# MainPCB.net
KiCad netlist of a schematic drawn in Altium Designer
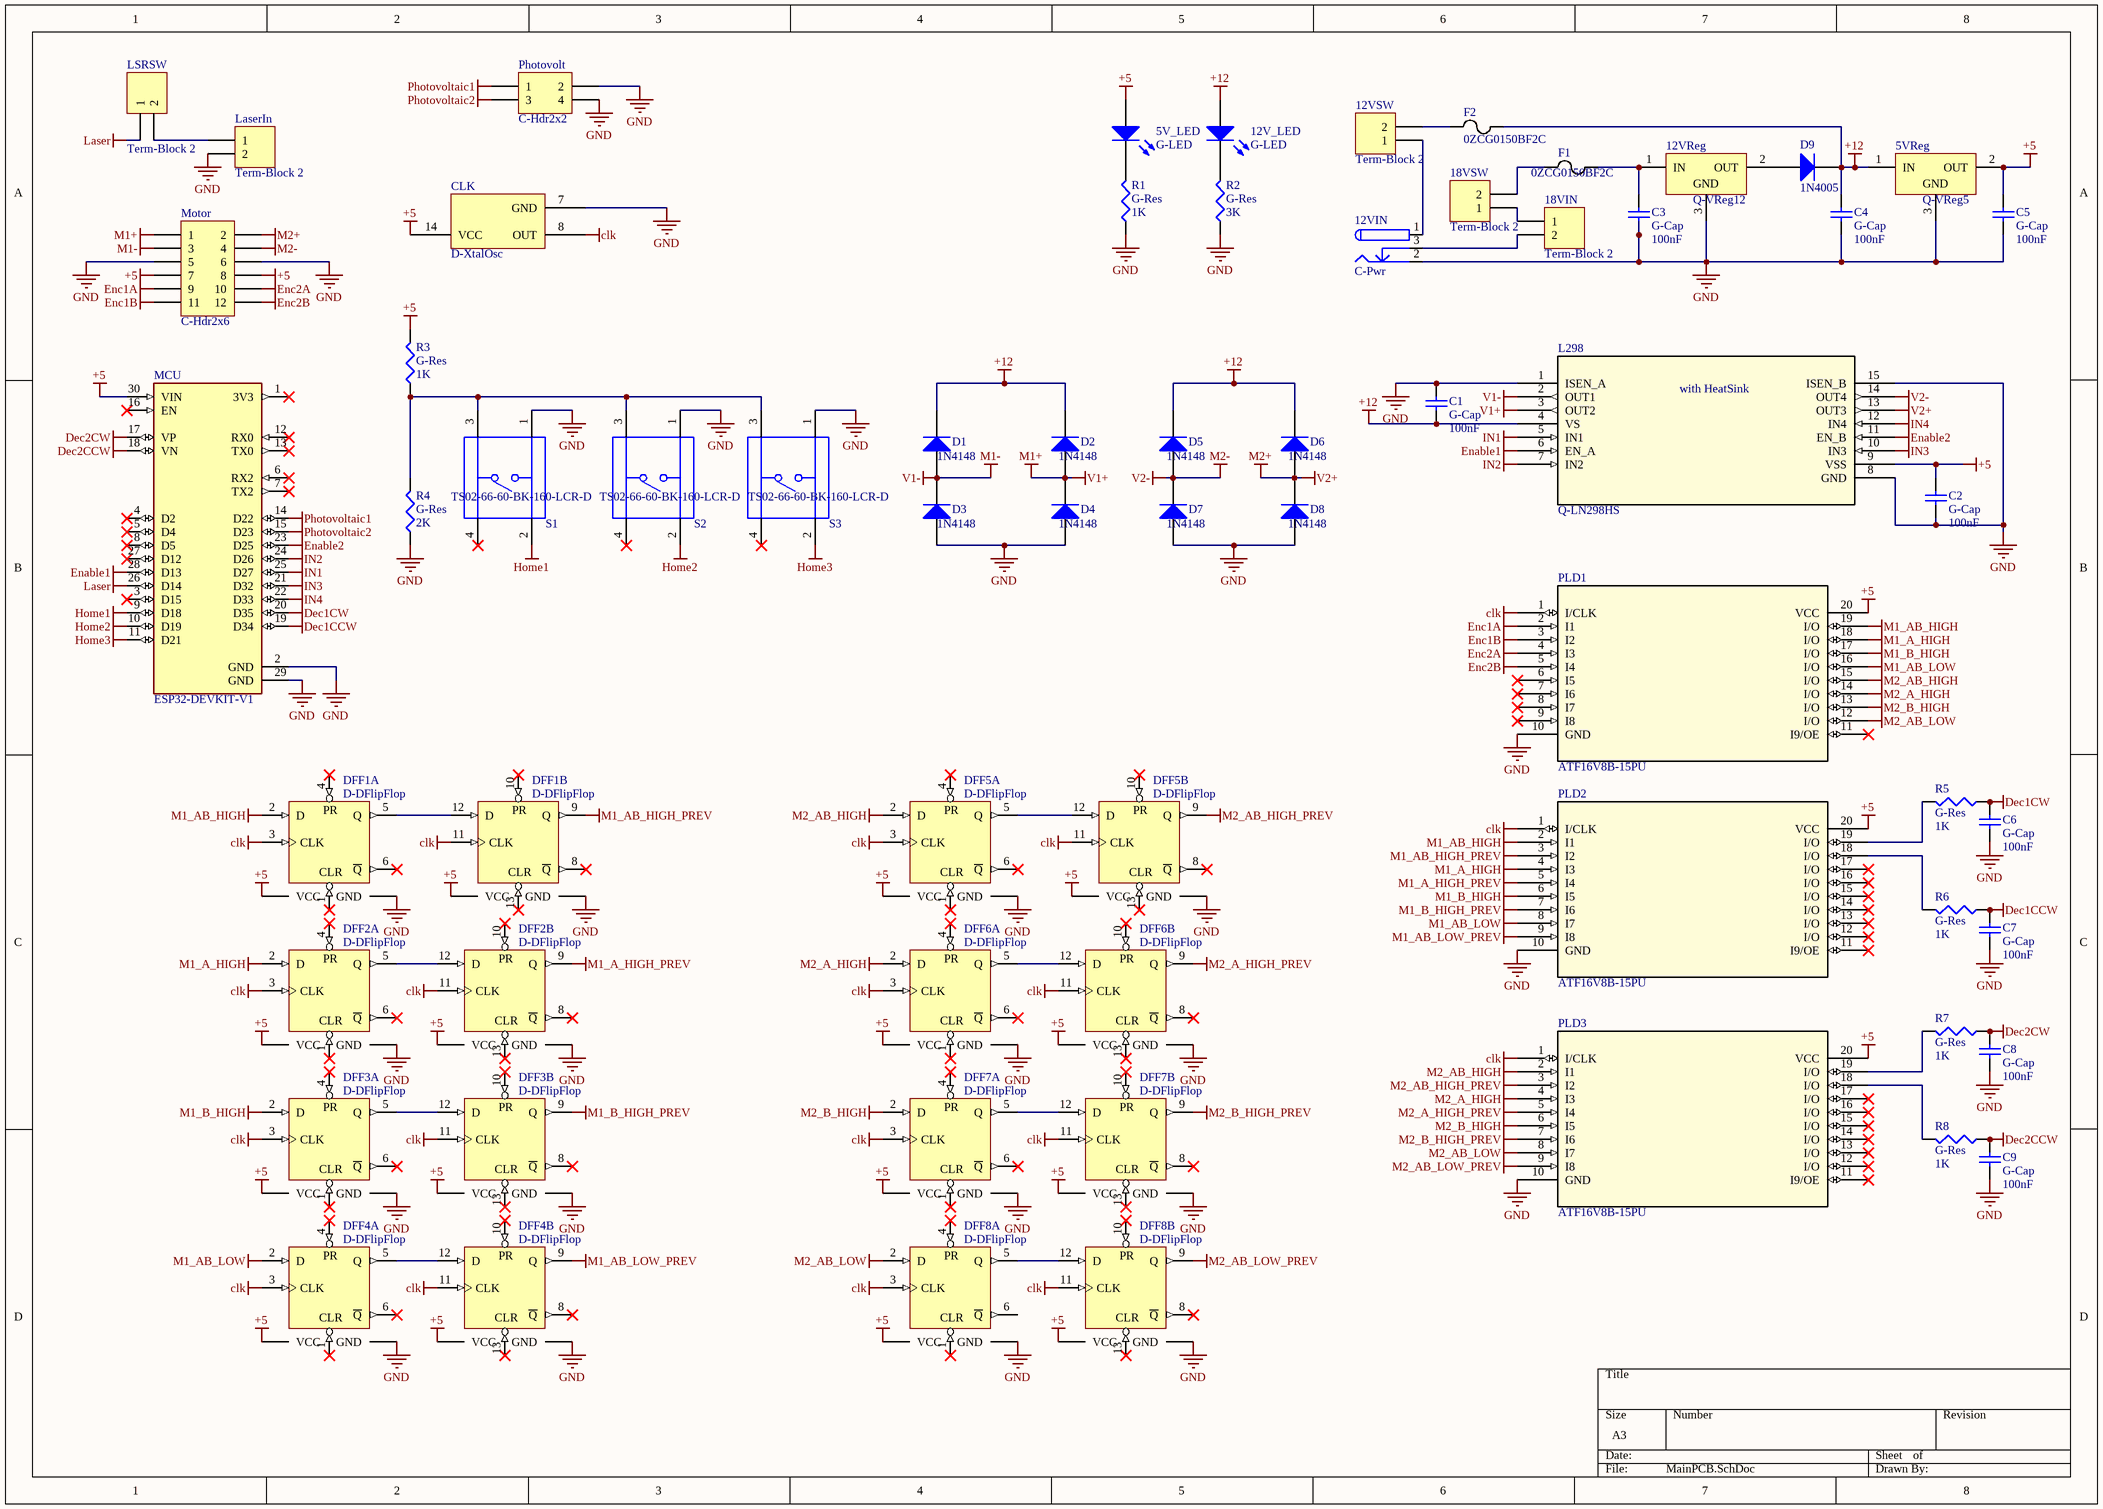
[diagram p0: MainPCB.SchDoc]

(export (version "E")
  (design (tool "Eeschema 10.0.6"))
  (components
    (comp (ref "5VReg")
      (value "Q-VReg5")
      (footprint "TO220_XLGE1.2")
      (description "voltage reg (5V)")
      (fields (field (name "PUBLISHER") "Altium Limited"))
      (libsource (lib "PartsDatabaseV16.1") (part "Q-VReg5"))
    )
    (comp (ref "5V_LED")
      (value "G-LED")
      (footprint "LED_LGE1.0")
      (description "Typical RED, GREEN, YELLOW, AMBER GaAs LED")
      (fields (field (name "PUBLISHER") "Altium Limited"))
      (libsource (lib "PartsDatabaseV16.1") (part "G-LED"))
    )
    (comp (ref "12VIN")
      (value "C-Pwr")
      (footprint "KLD_XLGE1.2")
      (description "Low Voltage Power Supply Connector")
      (fields (field (name "PUBLISHER") "Altium Limited"))
      (libsource (lib "PartsDatabaseV16.1") (part "C-Pwr"))
    )
    (comp (ref "12VReg")
      (value "Q-VReg12")
      (footprint "TO220_XLGE1.2")
      (description "voltage reg (12V)")
      (libsource (lib "PartsDatabaseV16.1") (part "Q-VReg12"))
    )
    (comp (ref "12VSW")
      (value "Term-Block 2")
      (footprint "TERM-BLOCK-5.08MM-2POS")
      (description "Terminal-Block 1x2")
      (fields (field (name "PUBLISHER") "Altium Limited"))
      (libsource (lib "") (part "C-Block2_1"))
    )
    (comp (ref "12V_LED")
      (value "G-LED")
      (footprint "LED_LGE1.0")
      (description "Typical RED, GREEN, YELLOW, AMBER GaAs LED")
      (fields (field (name "PUBLISHER") "Altium Limited"))
      (libsource (lib "PartsDatabaseV16.1") (part "G-LED"))
    )
    (comp (ref "18VIN")
      (value "Term-Block 2")
      (footprint "TERM-BLOCK-5.08MM-2POS")
      (description "Terminal-Block 1x2")
      (fields (field (name "PUBLISHER") "Altium Limited"))
      (libsource (lib "PartsDatabaseV16.1") (part "C-Block2"))
    )
    (comp (ref "18VSW")
      (value "Term-Block 2")
      (footprint "TERM-BLOCK-5.08MM-2POS")
      (description "Terminal-Block 1x2")
      (fields (field (name "PUBLISHER") "Altium Limited"))
      (libsource (lib "") (part "C-Block2_1"))
    )
    (comp (ref "C1")
      (value "G-Cap")
      (footprint "Cap2.54mm_LGE1.0")
      (description "Capacitor (specify value)")
      (fields (field (name "ALTIUM_VALUE") "100nF") (field (name "PUBLISHER") "Altium Limited"))
      (libsource (lib "PartsDatabaseV16.1") (part "G-Cap"))
    )
    (comp (ref "C2")
      (value "G-Cap")
      (footprint "Cap2.54mm_LGE1.0")
      (description "Capacitor (specify value)")
      (fields (field (name "ALTIUM_VALUE") "100nF") (field (name "PUBLISHER") "Altium Limited"))
      (libsource (lib "PartsDatabaseV16.1") (part "G-Cap"))
    )
    (comp (ref "C3")
      (value "G-Cap")
      (footprint "Cap2.54mm_LGE1.0")
      (description "Capacitor (specify value)")
      (fields (field (name "ALTIUM_VALUE") "100nF") (field (name "PUBLISHER") "Altium Limited"))
      (libsource (lib "PartsDatabaseV16.1") (part "G-Cap"))
    )
    (comp (ref "C4")
      (value "G-Cap")
      (footprint "Cap2.54mm_LGE1.0")
      (description "Capacitor (specify value)")
      (fields (field (name "ALTIUM_VALUE") "100nF") (field (name "PUBLISHER") "Altium Limited"))
      (libsource (lib "PartsDatabaseV16.1") (part "G-Cap"))
    )
    (comp (ref "C5")
      (value "G-Cap")
      (footprint "Cap2.54mm_LGE1.0")
      (description "Capacitor (specify value)")
      (fields (field (name "ALTIUM_VALUE") "100nF") (field (name "PUBLISHER") "Altium Limited"))
      (libsource (lib "PartsDatabaseV16.1") (part "G-Cap"))
    )
    (comp (ref "C6")
      (value "G-Cap")
      (footprint "Cap2.54mm_LGE1.0")
      (description "Capacitor (specify value)")
      (fields (field (name "ALTIUM_VALUE") "100nF") (field (name "PUBLISHER") "Altium Limited"))
      (libsource (lib "PartsDatabaseV16.1") (part "G-Cap"))
    )
    (comp (ref "C7")
      (value "G-Cap")
      (footprint "Cap2.54mm_LGE1.0")
      (description "Capacitor (specify value)")
      (fields (field (name "ALTIUM_VALUE") "100nF") (field (name "PUBLISHER") "Altium Limited"))
      (libsource (lib "PartsDatabaseV16.1") (part "G-Cap"))
    )
    (comp (ref "C8")
      (value "G-Cap")
      (footprint "Cap2.54mm_LGE1.0")
      (description "Capacitor (specify value)")
      (fields (field (name "ALTIUM_VALUE") "100nF") (field (name "PUBLISHER") "Altium Limited"))
      (libsource (lib "PartsDatabaseV16.1") (part "G-Cap"))
    )
    (comp (ref "C9")
      (value "G-Cap")
      (footprint "Cap2.54mm_LGE1.0")
      (description "Capacitor (specify value)")
      (fields (field (name "ALTIUM_VALUE") "100nF") (field (name "PUBLISHER") "Altium Limited"))
      (libsource (lib "PartsDatabaseV16.1") (part "G-Cap"))
    )
    (comp (ref "CLK")
      (value "D-XtalOsc")
      (footprint "4Lead Osc_LGE1.0")
      (description "Crystal Oscillator")
      (fields (field (name "PUBLISHER") "Altium Limited"))
      (libsource (lib "PartsDatabaseV16.1") (part "D-XtalOsc"))
    )
    (comp (ref "D1")
      (value "1N4148")
      (footprint "DO-41_XLGE1.2")
      (description "High-speed Diode")
      (libsource (lib "PartsDatabaseV16.1") (part "T-DiodeRect"))
    )
    (comp (ref "D2")
      (value "1N4148")
      (footprint "DO-41_XLGE1.2")
      (description "High-speed Diode")
      (libsource (lib "PartsDatabaseV16.1") (part "T-DiodeRect"))
    )
    (comp (ref "D3")
      (value "1N4148")
      (footprint "DO-41_XLGE1.2")
      (description "High-speed Diode")
      (libsource (lib "PartsDatabaseV16.1") (part "T-DiodeRect"))
    )
    (comp (ref "D4")
      (value "1N4148")
      (footprint "DO-41_XLGE1.2")
      (description "High-speed Diode")
      (libsource (lib "PartsDatabaseV16.1") (part "T-DiodeRect"))
    )
    (comp (ref "D5")
      (value "1N4148")
      (footprint "DO-41_XLGE1.2")
      (description "High-speed Diode")
      (libsource (lib "PartsDatabaseV16.1") (part "T-DiodeRect"))
    )
    (comp (ref "D6")
      (value "1N4148")
      (footprint "DO-41_XLGE1.2")
      (description "High-speed Diode")
      (libsource (lib "PartsDatabaseV16.1") (part "T-DiodeRect"))
    )
    (comp (ref "D7")
      (value "1N4148")
      (footprint "DO-41_XLGE1.2")
      (description "High-speed Diode")
      (libsource (lib "PartsDatabaseV16.1") (part "T-DiodeRect"))
    )
    (comp (ref "D8")
      (value "1N4148")
      (footprint "DO-41_XLGE1.2")
      (description "High-speed Diode")
      (libsource (lib "PartsDatabaseV16.1") (part "T-DiodeRect"))
    )
    (comp (ref "D9")
      (value "1N4005")
      (footprint "DO-41_XLGE1.2")
      (description "Diode")
      (fields (field (name "PUBLISHER") "Altium Limited"))
      (libsource (lib "PartsDatabaseV16.1") (part "T-Diode1N4005"))
    )
    (comp (ref "DFF1")
      (value "D-DFlipFlop")
      (footprint "DIP14_LGE1.0")
      (description "Dual D flip-flop")
      (fields (field (name "PUBLISHER") "Altium Limited"))
      (libsource (lib "PartsDatabaseV16.1") (part "D-DFlipFlop"))
    )
    (comp (ref "DFF2")
      (value "D-DFlipFlop")
      (footprint "DIP14_LGE1.0")
      (description "Dual D flip-flop")
      (fields (field (name "PUBLISHER") "Altium Limited"))
      (libsource (lib "PartsDatabaseV16.1") (part "D-DFlipFlop"))
    )
    (comp (ref "DFF3")
      (value "D-DFlipFlop")
      (footprint "DIP14_LGE1.0")
      (description "Dual D flip-flop")
      (fields (field (name "PUBLISHER") "Altium Limited"))
      (libsource (lib "PartsDatabaseV16.1") (part "D-DFlipFlop"))
    )
    (comp (ref "DFF4")
      (value "D-DFlipFlop")
      (footprint "DIP14_LGE1.0")
      (description "Dual D flip-flop")
      (fields (field (name "PUBLISHER") "Altium Limited"))
      (libsource (lib "PartsDatabaseV16.1") (part "D-DFlipFlop"))
    )
    (comp (ref "DFF5")
      (value "D-DFlipFlop")
      (footprint "DIP14_LGE1.0")
      (description "Dual D flip-flop")
      (fields (field (name "PUBLISHER") "Altium Limited"))
      (libsource (lib "PartsDatabaseV16.1") (part "D-DFlipFlop"))
    )
    (comp (ref "DFF6")
      (value "D-DFlipFlop")
      (footprint "DIP14_LGE1.0")
      (description "Dual D flip-flop")
      (fields (field (name "PUBLISHER") "Altium Limited"))
      (libsource (lib "PartsDatabaseV16.1") (part "D-DFlipFlop"))
    )
    (comp (ref "DFF7")
      (value "D-DFlipFlop")
      (footprint "DIP14_LGE1.0")
      (description "Dual D flip-flop")
      (fields (field (name "PUBLISHER") "Altium Limited"))
      (libsource (lib "PartsDatabaseV16.1") (part "D-DFlipFlop"))
    )
    (comp (ref "DFF8")
      (value "D-DFlipFlop")
      (footprint "DIP14_LGE1.0")
      (description "Dual D flip-flop")
      (fields (field (name "PUBLISHER") "Altium Limited"))
      (libsource (lib "PartsDatabaseV16.1") (part "D-DFlipFlop"))
    )
    (comp (ref "F1")
      (value "0ZCG0150BF2C")
      (footprint "0ZCG_BEL")
      (description "PTC RESET FUSE 24V 1.5A 1812")
      (libsource (lib "0ZCG0150BF2C") (part "0ZCG0150BF2C"))
    )
    (comp (ref "F2")
      (value "0ZCG0150BF2C")
      (footprint "0ZCG_BEL")
      (description "PTC RESET FUSE 24V 1.5A 1812")
      (libsource (lib "0ZCG0150BF2C") (part "0ZCG0150BF2C"))
    )
    (comp (ref "L298")
      (value "Q-LN298HS")
      (footprint "Multiwatt15_V_ELEC391HS")
      (description "LN298 - IC Bridge Driver Par 15Multiwatt")
      (fields
        (field (name "MANUFACTURER_PART_NUMBER") "L298N")
        (field (name "COPYRIGHT") "Copyright (C) 2015 Accelerated Designs. All rights reserved")
      )
      (libsource (lib "AdditionalParts391") (part "Q-LN298HS"))
    )
    (comp (ref "LaserIn")
      (value "Term-Block 2")
      (footprint "TERM-BLOCK-5.08MM-2POS")
      (description "Terminal-Block 1x2")
      (fields (field (name "PUBLISHER") "Altium Limited"))
      (libsource (lib "PartsDatabaseV16.1") (part "C-Block2"))
    )
    (comp (ref "LSRSW")
      (value "Term-Block 2")
      (footprint "TERM-BLOCK-5.08MM-2POS")
      (description "Terminal-Block 1x2")
      (fields (field (name "PUBLISHER") "Altium Limited"))
      (libsource (lib "") (part "C-Block2_2"))
    )
    (comp (ref "MCU")
      (value "ESP32-DEVKIT-V1")
      (footprint "MODULE_ESP32_DEVKIT_V1")
      (fields (field (name "MF") "Do it"))
      (libsource (lib "ESP32-DEVKIT-V1") (part "ESP32-DEVKIT-V1"))
    )
    (comp (ref "Motor")
      (value "C-Hdr2x6")
      (footprint "HDR2X6_LGE1.0")
      (description "Header, 6-Pin, Dual row")
      (fields (field (name "PUBLISHER") "Altium Limited"))
      (libsource (lib "PartsDatabaseV16.1") (part "C-Hdr2x6"))
    )
    (comp (ref "Photovolt")
      (value "C-Hdr2x2")
      (footprint "HDR2X2_LGE1.0")
      (description "Header, 2-Pin, Dual row")
      (fields (field (name "PUBLISHER") "Altium Limited"))
      (libsource (lib "PartsDatabaseV16.1") (part "C-Hdr2x2"))
    )
    (comp (ref "PLD1")
      (value "ATF16V8B-15PU")
      (footprint "20P3_ATM")
      (description "No Description Available")
      (libsource (lib "ATF16V8B-15PU") (part "ATF16V8B-15PU"))
    )
    (comp (ref "PLD2")
      (value "ATF16V8B-15PU")
      (footprint "20P3_ATM")
      (description "No Description Available")
      (libsource (lib "ATF16V8B-15PU") (part "ATF16V8B-15PU"))
    )
    (comp (ref "PLD3")
      (value "ATF16V8B-15PU")
      (footprint "20P3_ATM")
      (description "No Description Available")
      (libsource (lib "ATF16V8B-15PU") (part "ATF16V8B-15PU"))
    )
    (comp (ref "R1")
      (value "G-Res")
      (footprint "Res10mm_LGE1.0")
      (description "Resistor (specify value)")
      (fields (field (name "ALTIUM_VALUE") "1K") (field (name "PUBLISHER") "Altium Limited"))
      (libsource (lib "PartsDatabaseV16.1") (part "G-Res"))
    )
    (comp (ref "R2")
      (value "G-Res")
      (footprint "Res10mm_LGE1.0")
      (description "Resistor (specify value)")
      (fields (field (name "ALTIUM_VALUE") "3K") (field (name "PUBLISHER") "Altium Limited"))
      (libsource (lib "PartsDatabaseV16.1") (part "G-Res"))
    )
    (comp (ref "R3")
      (value "G-Res")
      (footprint "Res10mm_LGE1.0")
      (description "Resistor (specify value)")
      (fields (field (name "ALTIUM_VALUE") "1K") (field (name "PUBLISHER") "Altium Limited"))
      (libsource (lib "PartsDatabaseV16.1") (part "G-Res"))
    )
    (comp (ref "R4")
      (value "G-Res")
      (footprint "Res10mm_LGE1.0")
      (description "Resistor (specify value)")
      (fields (field (name "ALTIUM_VALUE") "2K") (field (name "PUBLISHER") "Altium Limited"))
      (libsource (lib "PartsDatabaseV16.1") (part "G-Res"))
    )
    (comp (ref "R5")
      (value "G-Res")
      (footprint "Res10mm_LGE1.0")
      (description "Resistor (specify value)")
      (fields (field (name "ALTIUM_VALUE") "1K") (field (name "PUBLISHER") "Altium Limited"))
      (libsource (lib "PartsDatabaseV16.1") (part "G-Res"))
    )
    (comp (ref "R6")
      (value "G-Res")
      (footprint "Res10mm_LGE1.0")
      (description "Resistor (specify value)")
      (fields (field (name "ALTIUM_VALUE") "1K") (field (name "PUBLISHER") "Altium Limited"))
      (libsource (lib "PartsDatabaseV16.1") (part "G-Res"))
    )
    (comp (ref "R7")
      (value "G-Res")
      (footprint "Res10mm_LGE1.0")
      (description "Resistor (specify value)")
      (fields (field (name "ALTIUM_VALUE") "1K") (field (name "PUBLISHER") "Altium Limited"))
      (libsource (lib "PartsDatabaseV16.1") (part "G-Res"))
    )
    (comp (ref "R8")
      (value "G-Res")
      (footprint "Res10mm_LGE1.0")
      (description "Resistor (specify value)")
      (fields (field (name "ALTIUM_VALUE") "1K") (field (name "PUBLISHER") "Altium Limited"))
      (libsource (lib "PartsDatabaseV16.1") (part "G-Res"))
    )
    (comp (ref "S1")
      (value "TS02-66-60-BK-160-LCR-D")
      (footprint "SW_TS02-66-60-BK-160-LCR-D")
      (description "6 x 6 mm, 6 mm Actuator Height, 160 gf, Black, Long Crimped, Through Hole, SPST, Tactile Switch")
      (fields (field (name "MF") "CUI Devices"))
      (libsource (lib "TS02-66-60-BK-160-LCR-D") (part "TS02-66-60-BK-160-LCR-D"))
    )
    (comp (ref "S2")
      (value "TS02-66-60-BK-160-LCR-D")
      (footprint "SW_TS02-66-60-BK-160-LCR-D")
      (description "6 x 6 mm, 6 mm Actuator Height, 160 gf, Black, Long Crimped, Through Hole, SPST, Tactile Switch")
      (fields (field (name "MF") "CUI Devices"))
      (libsource (lib "TS02-66-60-BK-160-LCR-D") (part "TS02-66-60-BK-160-LCR-D"))
    )
    (comp (ref "S3")
      (value "TS02-66-60-BK-160-LCR-D")
      (footprint "SW_TS02-66-60-BK-160-LCR-D")
      (description "6 x 6 mm, 6 mm Actuator Height, 160 gf, Black, Long Crimped, Through Hole, SPST, Tactile Switch")
      (fields (field (name "MF") "CUI Devices"))
      (libsource (lib "TS02-66-60-BK-160-LCR-D") (part "TS02-66-60-BK-160-LCR-D"))
    )
  )
  (nets
    (net (code "1") (name "+5") (class "Default")
      (node (ref "5VReg") (pin "2") (pinfunction "OUT_2") (pintype "power_in"))
      (node (ref "5V_LED") (pin "1") (pinfunction "A_1") (pintype "passive"))
      (node (ref "C2") (pin "1") (pinfunction "1_1") (pintype "passive"))
      (node (ref "C5") (pin "1") (pinfunction "1_1") (pintype "passive"))
      (node (ref "CLK") (pin "14") (pinfunction "VCC_14") (pintype "passive"))
      (node (ref "DFF1") (pin "14") (pinfunction "VCC_14") (pintype "power_in"))
      (node (ref "DFF2") (pin "14") (pinfunction "VCC_14") (pintype "power_in"))
      (node (ref "DFF3") (pin "14") (pinfunction "VCC_14") (pintype "power_in"))
      (node (ref "DFF4") (pin "14") (pinfunction "VCC_14") (pintype "power_in"))
      (node (ref "DFF5") (pin "14") (pinfunction "VCC_14") (pintype "power_in"))
      (node (ref "DFF6") (pin "14") (pinfunction "VCC_14") (pintype "power_in"))
      (node (ref "DFF7") (pin "14") (pinfunction "VCC_14") (pintype "power_in"))
      (node (ref "DFF8") (pin "14") (pinfunction "VCC_14") (pintype "power_in"))
      (node (ref "L298") (pin "9") (pinfunction "VSS_9") (pintype "power_in"))
      (node (ref "MCU") (pin "30") (pinfunction "VIN_30") (pintype "input"))
      (node (ref "Motor") (pin "7") (pinfunction "7_7") (pintype "passive"))
      (node (ref "Motor") (pin "8") (pinfunction "8_8") (pintype "passive"))
      (node (ref "PLD1") (pin "20") (pinfunction "VCC_20") (pintype "power_in"))
      (node (ref "PLD2") (pin "20") (pinfunction "VCC_20") (pintype "power_in"))
      (node (ref "PLD3") (pin "20") (pinfunction "VCC_20") (pintype "power_in"))
      (node (ref "R3") (pin "2") (pinfunction "2_2") (pintype "passive"))
    )
    (net (code "2") (name "+12") (class "Default")
      (node (ref "12V_LED") (pin "1") (pinfunction "A_1") (pintype "passive"))
      (node (ref "5VReg") (pin "1") (pinfunction "IN_1") (pintype "power_in"))
      (node (ref "C1") (pin "2") (pinfunction "2_2") (pintype "passive"))
      (node (ref "C4") (pin "1") (pinfunction "1_1") (pintype "passive"))
      (node (ref "D1") (pin "2") (pinfunction "K_2") (pintype "passive"))
      (node (ref "D2") (pin "2") (pinfunction "K_2") (pintype "passive"))
      (node (ref "D5") (pin "2") (pinfunction "K_2") (pintype "passive"))
      (node (ref "D6") (pin "2") (pinfunction "K_2") (pintype "passive"))
      (node (ref "D9") (pin "2") (pinfunction "K_2") (pintype "passive"))
      (node (ref "F2") (pin "2") (pinfunction "2_2") (pintype "passive"))
      (node (ref "L298") (pin "4") (pinfunction "VS_4") (pintype "power_in"))
    )
    (net (code "3") (name "Dec1CCW") (class "Default")
      (node (ref "C7") (pin "1") (pinfunction "1_1") (pintype "passive"))
      (node (ref "MCU") (pin "19") (pinfunction "D34_19") (pintype "bidirectional"))
      (node (ref "R6") (pin "1") (pinfunction "1_1") (pintype "passive"))
    )
    (net (code "4") (name "Dec1CW") (class "Default")
      (node (ref "C6") (pin "1") (pinfunction "1_1") (pintype "passive"))
      (node (ref "MCU") (pin "20") (pinfunction "D35_20") (pintype "bidirectional"))
      (node (ref "R5") (pin "1") (pinfunction "1_1") (pintype "passive"))
    )
    (net (code "5") (name "Dec2CCW") (class "Default")
      (node (ref "C9") (pin "1") (pinfunction "1_1") (pintype "passive"))
      (node (ref "MCU") (pin "18") (pinfunction "VN_18") (pintype "bidirectional"))
      (node (ref "R8") (pin "1") (pinfunction "1_1") (pintype "passive"))
    )
    (net (code "6") (name "Dec2CW") (class "Default")
      (node (ref "C8") (pin "1") (pinfunction "1_1") (pintype "passive"))
      (node (ref "MCU") (pin "17") (pinfunction "VP_17") (pintype "bidirectional"))
      (node (ref "R7") (pin "1") (pinfunction "1_1") (pintype "passive"))
    )
    (net (code "7") (name "Enable1") (class "Default")
      (node (ref "L298") (pin "6") (pinfunction "EN_A_6") (pintype "input"))
      (node (ref "MCU") (pin "28") (pinfunction "D13_28") (pintype "bidirectional"))
    )
    (net (code "8") (name "Enable2") (class "Default")
      (node (ref "L298") (pin "11") (pinfunction "EN_B_11") (pintype "input"))
      (node (ref "MCU") (pin "23") (pinfunction "D25_23") (pintype "bidirectional"))
    )
    (net (code "9") (name "Enc1A") (class "Default")
      (node (ref "Motor") (pin "9") (pinfunction "9_9") (pintype "passive"))
      (node (ref "PLD1") (pin "2") (pinfunction "I1_2") (pintype "input"))
    )
    (net (code "10") (name "Enc1B") (class "Default")
      (node (ref "Motor") (pin "11") (pinfunction "11_11") (pintype "passive"))
      (node (ref "PLD1") (pin "3") (pinfunction "I2_3") (pintype "input"))
    )
    (net (code "11") (name "Enc2A") (class "Default")
      (node (ref "Motor") (pin "10") (pinfunction "10_10") (pintype "passive"))
      (node (ref "PLD1") (pin "4") (pinfunction "I3_4") (pintype "input"))
    )
    (net (code "12") (name "Enc2B") (class "Default")
      (node (ref "Motor") (pin "12") (pinfunction "12_12") (pintype "passive"))
      (node (ref "PLD1") (pin "5") (pinfunction "I4_5") (pintype "input"))
    )
    (net (code "13") (name "GND") (class "Default")
      (node (ref "12VIN") (pin "2") (pinfunction "2_2") (pintype "power_in"))
      (node (ref "12VReg") (pin "3") (pinfunction "GND_3") (pintype "power_in"))
      (node (ref "5VReg") (pin "3") (pinfunction "GND_3") (pintype "power_in"))
      (node (ref "C1") (pin "1") (pinfunction "1_1") (pintype "passive"))
      (node (ref "C2") (pin "2") (pinfunction "2_2") (pintype "passive"))
      (node (ref "C3") (pin "2") (pinfunction "2_2") (pintype "passive"))
      (node (ref "C4") (pin "2") (pinfunction "2_2") (pintype "passive"))
      (node (ref "C5") (pin "2") (pinfunction "2_2") (pintype "passive"))
      (node (ref "C6") (pin "2") (pinfunction "2_2") (pintype "passive"))
      (node (ref "C7") (pin "2") (pinfunction "2_2") (pintype "passive"))
      (node (ref "C8") (pin "2") (pinfunction "2_2") (pintype "passive"))
      (node (ref "C9") (pin "2") (pinfunction "2_2") (pintype "passive"))
      (node (ref "CLK") (pin "7") (pinfunction "GND_7") (pintype "passive"))
      (node (ref "D3") (pin "1") (pinfunction "A_1") (pintype "passive"))
      (node (ref "D4") (pin "1") (pinfunction "A_1") (pintype "passive"))
      (node (ref "D7") (pin "1") (pinfunction "A_1") (pintype "passive"))
      (node (ref "D8") (pin "1") (pinfunction "A_1") (pintype "passive"))
      (node (ref "DFF1") (pin "7") (pinfunction "GND_7") (pintype "power_in"))
      (node (ref "DFF2") (pin "7") (pinfunction "GND_7") (pintype "power_in"))
      (node (ref "DFF3") (pin "7") (pinfunction "GND_7") (pintype "power_in"))
      (node (ref "DFF4") (pin "7") (pinfunction "GND_7") (pintype "power_in"))
      (node (ref "DFF5") (pin "7") (pinfunction "GND_7") (pintype "power_in"))
      (node (ref "DFF6") (pin "7") (pinfunction "GND_7") (pintype "power_in"))
      (node (ref "DFF7") (pin "7") (pinfunction "GND_7") (pintype "power_in"))
      (node (ref "DFF8") (pin "7") (pinfunction "GND_7") (pintype "power_in"))
      (node (ref "L298") (pin "1") (pinfunction "ISEN_A_1") (pintype "passive"))
      (node (ref "L298") (pin "15") (pinfunction "ISEN_B_15") (pintype "passive"))
      (node (ref "L298") (pin "8") (pinfunction "GND_8") (pintype "power_in"))
      (node (ref "LaserIn") (pin "2") (pinfunction "2_2") (pintype "passive"))
      (node (ref "MCU") (pin "2") (pinfunction "GND_2") (pintype "power_in"))
      (node (ref "MCU") (pin "29") (pinfunction "GND_29") (pintype "power_in"))
      (node (ref "Motor") (pin "5") (pinfunction "5_5") (pintype "passive"))
      (node (ref "Motor") (pin "6") (pinfunction "6_6") (pintype "passive"))
      (node (ref "PLD1") (pin "10") (pinfunction "GND_10") (pintype "power_in"))
      (node (ref "PLD2") (pin "10") (pinfunction "GND_10") (pintype "power_in"))
      (node (ref "PLD3") (pin "10") (pinfunction "GND_10") (pintype "power_in"))
      (node (ref "Photovolt") (pin "2") (pinfunction "2_2") (pintype "passive"))
      (node (ref "Photovolt") (pin "4") (pinfunction "4_4") (pintype "passive"))
      (node (ref "R1") (pin "1") (pinfunction "1_1") (pintype "passive"))
      (node (ref "R2") (pin "1") (pinfunction "1_1") (pintype "passive"))
      (node (ref "R4") (pin "1") (pinfunction "1_1") (pintype "passive"))
      (node (ref "S1") (pin "1") (pinfunction "1_1") (pintype "passive"))
      (node (ref "S2") (pin "1") (pinfunction "1_1") (pintype "passive"))
      (node (ref "S3") (pin "1") (pinfunction "1_1") (pintype "passive"))
    )
    (net (code "14") (name "Home1") (class "Default")
      (node (ref "MCU") (pin "9") (pinfunction "D18_9") (pintype "bidirectional"))
      (node (ref "S1") (pin "2") (pinfunction "2_2") (pintype "passive"))
    )
    (net (code "15") (name "Home2") (class "Default")
      (node (ref "MCU") (pin "10") (pinfunction "D19_10") (pintype "bidirectional"))
      (node (ref "S2") (pin "2") (pinfunction "2_2") (pintype "passive"))
    )
    (net (code "16") (name "Home3") (class "Default")
      (node (ref "MCU") (pin "11") (pinfunction "D21_11") (pintype "bidirectional"))
      (node (ref "S3") (pin "2") (pinfunction "2_2") (pintype "passive"))
    )
    (net (code "17") (name "IN1") (class "Default")
      (node (ref "L298") (pin "5") (pinfunction "IN1_5") (pintype "input"))
      (node (ref "MCU") (pin "25") (pinfunction "D27_25") (pintype "bidirectional"))
    )
    (net (code "18") (name "IN2") (class "Default")
      (node (ref "L298") (pin "7") (pinfunction "IN2_7") (pintype "input"))
      (node (ref "MCU") (pin "24") (pinfunction "D26_24") (pintype "bidirectional"))
    )
    (net (code "19") (name "IN3") (class "Default")
      (node (ref "L298") (pin "10") (pinfunction "IN3_10") (pintype "input"))
      (node (ref "MCU") (pin "21") (pinfunction "D32_21") (pintype "bidirectional"))
    )
    (net (code "20") (name "IN4") (class "Default")
      (node (ref "L298") (pin "12") (pinfunction "IN4_12") (pintype "input"))
      (node (ref "MCU") (pin "22") (pinfunction "D33_22") (pintype "bidirectional"))
    )
    (net (code "21") (name "Laser") (class "Default")
      (node (ref "LSRSW") (pin "1") (pinfunction "1_1") (pintype "passive"))
      (node (ref "MCU") (pin "26") (pinfunction "D14_26") (pintype "bidirectional"))
    )
    (net (code "22") (name "M1+") (class "Default")
      (node (ref "D2") (pin "1") (pinfunction "A_1") (pintype "passive"))
      (node (ref "D4") (pin "2") (pinfunction "K_2") (pintype "passive"))
      (node (ref "L298") (pin "3") (pinfunction "OUT2_3") (pintype "output"))
      (node (ref "Motor") (pin "1") (pinfunction "1_1") (pintype "passive"))
    )
    (net (code "23") (name "M1-") (class "Default")
      (node (ref "D1") (pin "1") (pinfunction "A_1") (pintype "passive"))
      (node (ref "D3") (pin "2") (pinfunction "K_2") (pintype "passive"))
      (node (ref "L298") (pin "2") (pinfunction "OUT1_2") (pintype "output"))
      (node (ref "Motor") (pin "3") (pinfunction "3_3") (pintype "passive"))
    )
    (net (code "24") (name "M1_AB_HIGH") (class "Default")
      (node (ref "DFF1") (pin "2") (pinfunction "D_2") (pintype "input"))
      (node (ref "PLD1") (pin "19") (pinfunction "I/O_19") (pintype "bidirectional"))
      (node (ref "PLD2") (pin "2") (pinfunction "I1_2") (pintype "input"))
    )
    (net (code "25") (name "M1_AB_HIGH_PREV") (class "Default")
      (node (ref "DFF1") (pin "9") (pinfunction "Q_9") (pintype "output"))
      (node (ref "PLD2") (pin "3") (pinfunction "I2_3") (pintype "input"))
    )
    (net (code "26") (name "M1_AB_LOW") (class "Default")
      (node (ref "DFF4") (pin "2") (pinfunction "D_2") (pintype "input"))
      (node (ref "PLD1") (pin "16") (pinfunction "I/O_16") (pintype "bidirectional"))
      (node (ref "PLD2") (pin "8") (pinfunction "I7_8") (pintype "input"))
    )
    (net (code "27") (name "M1_AB_LOW_PREV") (class "Default")
      (node (ref "DFF4") (pin "9") (pinfunction "Q_9") (pintype "output"))
      (node (ref "PLD2") (pin "9") (pinfunction "I8_9") (pintype "input"))
    )
    (net (code "28") (name "M1_A_HIGH") (class "Default")
      (node (ref "DFF2") (pin "2") (pinfunction "D_2") (pintype "input"))
      (node (ref "PLD1") (pin "18") (pinfunction "I/O_18") (pintype "bidirectional"))
      (node (ref "PLD2") (pin "4") (pinfunction "I3_4") (pintype "input"))
    )
    (net (code "29") (name "M1_A_HIGH_PREV") (class "Default")
      (node (ref "DFF2") (pin "9") (pinfunction "Q_9") (pintype "output"))
      (node (ref "PLD2") (pin "5") (pinfunction "I4_5") (pintype "input"))
    )
    (net (code "30") (name "M1_B_HIGH") (class "Default")
      (node (ref "DFF3") (pin "2") (pinfunction "D_2") (pintype "input"))
      (node (ref "PLD1") (pin "17") (pinfunction "I/O_17") (pintype "bidirectional"))
      (node (ref "PLD2") (pin "6") (pinfunction "I5_6") (pintype "input"))
    )
    (net (code "31") (name "M1_B_HIGH_PREV") (class "Default")
      (node (ref "DFF3") (pin "9") (pinfunction "Q_9") (pintype "output"))
      (node (ref "PLD2") (pin "7") (pinfunction "I6_7") (pintype "input"))
    )
    (net (code "32") (name "M2+") (class "Default")
      (node (ref "D6") (pin "1") (pinfunction "A_1") (pintype "passive"))
      (node (ref "D8") (pin "2") (pinfunction "K_2") (pintype "passive"))
      (node (ref "L298") (pin "13") (pinfunction "OUT3_13") (pintype "output"))
      (node (ref "Motor") (pin "2") (pinfunction "2_2") (pintype "passive"))
    )
    (net (code "33") (name "M2-") (class "Default")
      (node (ref "D5") (pin "1") (pinfunction "A_1") (pintype "passive"))
      (node (ref "D7") (pin "2") (pinfunction "K_2") (pintype "passive"))
      (node (ref "L298") (pin "14") (pinfunction "OUT4_14") (pintype "output"))
      (node (ref "Motor") (pin "4") (pinfunction "4_4") (pintype "passive"))
    )
    (net (code "34") (name "M2_AB_HIGH") (class "Default")
      (node (ref "DFF5") (pin "2") (pinfunction "D_2") (pintype "input"))
      (node (ref "PLD1") (pin "15") (pinfunction "I/O_15") (pintype "bidirectional"))
      (node (ref "PLD3") (pin "2") (pinfunction "I1_2") (pintype "input"))
    )
    (net (code "35") (name "M2_AB_HIGH_PREV") (class "Default")
      (node (ref "DFF5") (pin "9") (pinfunction "Q_9") (pintype "output"))
      (node (ref "PLD3") (pin "3") (pinfunction "I2_3") (pintype "input"))
    )
    (net (code "36") (name "M2_AB_LOW") (class "Default")
      (node (ref "DFF8") (pin "2") (pinfunction "D_2") (pintype "input"))
      (node (ref "PLD1") (pin "12") (pinfunction "I/O_12") (pintype "bidirectional"))
      (node (ref "PLD3") (pin "8") (pinfunction "I7_8") (pintype "input"))
    )
    (net (code "37") (name "M2_AB_LOW_PREV") (class "Default")
      (node (ref "DFF8") (pin "9") (pinfunction "Q_9") (pintype "output"))
      (node (ref "PLD3") (pin "9") (pinfunction "I8_9") (pintype "input"))
    )
    (net (code "38") (name "M2_A_HIGH") (class "Default")
      (node (ref "DFF6") (pin "2") (pinfunction "D_2") (pintype "input"))
      (node (ref "PLD1") (pin "14") (pinfunction "I/O_14") (pintype "bidirectional"))
      (node (ref "PLD3") (pin "4") (pinfunction "I3_4") (pintype "input"))
    )
    (net (code "39") (name "M2_A_HIGH_PREV") (class "Default")
      (node (ref "DFF6") (pin "9") (pinfunction "Q_9") (pintype "output"))
      (node (ref "PLD3") (pin "5") (pinfunction "I4_5") (pintype "input"))
    )
    (net (code "40") (name "M2_B_HIGH") (class "Default")
      (node (ref "DFF7") (pin "2") (pinfunction "D_2") (pintype "input"))
      (node (ref "PLD1") (pin "13") (pinfunction "I/O_13") (pintype "bidirectional"))
      (node (ref "PLD3") (pin "6") (pinfunction "I5_6") (pintype "input"))
    )
    (net (code "41") (name "M2_B_HIGH_PREV") (class "Default")
      (node (ref "DFF7") (pin "9") (pinfunction "Q_9") (pintype "output"))
      (node (ref "PLD3") (pin "7") (pinfunction "I6_7") (pintype "input"))
    )
    (net (code "42") (name "Net-(5V_LED-K)") (class "Default")
      (node (ref "5V_LED") (pin "2") (pinfunction "K_2") (pintype "passive"))
      (node (ref "R1") (pin "2") (pinfunction "2_2") (pintype "passive"))
    )
    (net (code "43") (name "Net-(12VIN-Pad1)") (class "Default")
      (node (ref "12VIN") (pin "1") (pinfunction "1_1") (pintype "power_in"))
      (node (ref "12VSW") (pin "1") (pinfunction "1_1") (pintype "passive"))
    )
    (net (code "44") (name "Net-(12VIN-Pad3)") (class "Default")
      (node (ref "12VIN") (pin "3") (pinfunction "3_3") (pintype "power_in"))
      (node (ref "18VIN") (pin "2") (pinfunction "2_2") (pintype "passive"))
    )
    (net (code "45") (name "Net-(12VReg-IN)") (class "Default")
      (node (ref "12VReg") (pin "1") (pinfunction "IN_1") (pintype "power_in"))
      (node (ref "C3") (pin "1") (pinfunction "1_1") (pintype "passive"))
      (node (ref "F1") (pin "2") (pinfunction "2_2") (pintype "passive"))
    )
    (net (code "46") (name "Net-(12VReg-OUT)") (class "Default")
      (node (ref "12VReg") (pin "2") (pinfunction "OUT_2") (pintype "power_in"))
      (node (ref "D9") (pin "1") (pinfunction "A_1") (pintype "passive"))
    )
    (net (code "47") (name "Net-(12VSW-Pad2)") (class "Default")
      (node (ref "12VSW") (pin "2") (pinfunction "2_2") (pintype "passive"))
      (node (ref "F2") (pin "1") (pinfunction "1_1") (pintype "passive"))
    )
    (net (code "48") (name "Net-(12V_LED-K)") (class "Default")
      (node (ref "12V_LED") (pin "2") (pinfunction "K_2") (pintype "passive"))
      (node (ref "R2") (pin "2") (pinfunction "2_2") (pintype "passive"))
    )
    (net (code "49") (name "Net-(18VIN-Pad1)") (class "Default")
      (node (ref "18VIN") (pin "1") (pinfunction "1_1") (pintype "passive"))
      (node (ref "18VSW") (pin "1") (pinfunction "1_1") (pintype "passive"))
    )
    (net (code "50") (name "Net-(18VSW-Pad2)") (class "Default")
      (node (ref "18VSW") (pin "2") (pinfunction "2_2") (pintype "passive"))
      (node (ref "F1") (pin "1") (pinfunction "1_1") (pintype "passive"))
    )
    (net (code "51") (name "Net-(DFF1A-Q)") (class "Default")
      (node (ref "DFF1") (pin "12") (pinfunction "D_12") (pintype "input"))
      (node (ref "DFF1") (pin "5") (pinfunction "Q_5") (pintype "output"))
    )
    (net (code "52") (name "Net-(DFF2A-Q)") (class "Default")
      (node (ref "DFF2") (pin "12") (pinfunction "D_12") (pintype "input"))
      (node (ref "DFF2") (pin "5") (pinfunction "Q_5") (pintype "output"))
    )
    (net (code "53") (name "Net-(DFF3A-Q)") (class "Default")
      (node (ref "DFF3") (pin "12") (pinfunction "D_12") (pintype "input"))
      (node (ref "DFF3") (pin "5") (pinfunction "Q_5") (pintype "output"))
    )
    (net (code "54") (name "Net-(DFF4A-Q)") (class "Default")
      (node (ref "DFF4") (pin "12") (pinfunction "D_12") (pintype "input"))
      (node (ref "DFF4") (pin "5") (pinfunction "Q_5") (pintype "output"))
    )
    (net (code "55") (name "Net-(DFF5A-Q)") (class "Default")
      (node (ref "DFF5") (pin "12") (pinfunction "D_12") (pintype "input"))
      (node (ref "DFF5") (pin "5") (pinfunction "Q_5") (pintype "output"))
    )
    (net (code "56") (name "Net-(DFF6A-Q)") (class "Default")
      (node (ref "DFF6") (pin "12") (pinfunction "D_12") (pintype "input"))
      (node (ref "DFF6") (pin "5") (pinfunction "Q_5") (pintype "output"))
    )
    (net (code "57") (name "Net-(DFF7A-Q)") (class "Default")
      (node (ref "DFF7") (pin "12") (pinfunction "D_12") (pintype "input"))
      (node (ref "DFF7") (pin "5") (pinfunction "Q_5") (pintype "output"))
    )
    (net (code "58") (name "Net-(DFF8A-Q)") (class "Default")
      (node (ref "DFF8") (pin "12") (pinfunction "D_12") (pintype "input"))
      (node (ref "DFF8") (pin "5") (pinfunction "Q_5") (pintype "output"))
    )
    (net (code "59") (name "Net-(LSRSW-Pad2)") (class "Default")
      (node (ref "LSRSW") (pin "2") (pinfunction "2_2") (pintype "passive"))
      (node (ref "LaserIn") (pin "1") (pinfunction "1_1") (pintype "passive"))
    )
    (net (code "60") (name "Net-(PLD2-I{slash}O-Pad18)") (class "Default")
      (node (ref "PLD2") (pin "18") (pinfunction "I/O_18") (pintype "bidirectional"))
      (node (ref "R6") (pin "2") (pinfunction "2_2") (pintype "passive"))
    )
    (net (code "61") (name "Net-(PLD2-I{slash}O-Pad19)") (class "Default")
      (node (ref "PLD2") (pin "19") (pinfunction "I/O_19") (pintype "bidirectional"))
      (node (ref "R5") (pin "2") (pinfunction "2_2") (pintype "passive"))
    )
    (net (code "62") (name "Net-(PLD3-I{slash}O-Pad18)") (class "Default")
      (node (ref "PLD3") (pin "18") (pinfunction "I/O_18") (pintype "bidirectional"))
      (node (ref "R8") (pin "2") (pinfunction "2_2") (pintype "passive"))
    )
    (net (code "63") (name "Net-(PLD3-I{slash}O-Pad19)") (class "Default")
      (node (ref "PLD3") (pin "19") (pinfunction "I/O_19") (pintype "bidirectional"))
      (node (ref "R7") (pin "2") (pinfunction "2_2") (pintype "passive"))
    )
    (net (code "64") (name "Net-(R3-Pad1)") (class "Default")
      (node (ref "R3") (pin "1") (pinfunction "1_1") (pintype "passive"))
      (node (ref "R4") (pin "2") (pinfunction "2_2") (pintype "passive"))
      (node (ref "S1") (pin "3") (pinfunction "3_3") (pintype "passive"))
      (node (ref "S2") (pin "3") (pinfunction "3_3") (pintype "passive"))
      (node (ref "S3") (pin "3") (pinfunction "3_3") (pintype "passive"))
    )
    (net (code "65") (name "Photovoltaic1") (class "Default")
      (node (ref "MCU") (pin "14") (pinfunction "D22_14") (pintype "bidirectional"))
      (node (ref "Photovolt") (pin "1") (pinfunction "1_1") (pintype "passive"))
    )
    (net (code "66") (name "Photovoltaic2") (class "Default")
      (node (ref "MCU") (pin "15") (pinfunction "D23_15") (pintype "bidirectional"))
      (node (ref "Photovolt") (pin "3") (pinfunction "3_3") (pintype "passive"))
    )
    (net (code "67") (name "clk") (class "Default")
      (node (ref "CLK") (pin "8") (pinfunction "OUT_8") (pintype "passive"))
      (node (ref "DFF1") (pin "11") (pinfunction "CLK_11") (pintype "input"))
      (node (ref "DFF1") (pin "3") (pinfunction "CLK_3") (pintype "input"))
      (node (ref "DFF2") (pin "11") (pinfunction "CLK_11") (pintype "input"))
      (node (ref "DFF2") (pin "3") (pinfunction "CLK_3") (pintype "input"))
      (node (ref "DFF3") (pin "11") (pinfunction "CLK_11") (pintype "input"))
      (node (ref "DFF3") (pin "3") (pinfunction "CLK_3") (pintype "input"))
      (node (ref "DFF4") (pin "11") (pinfunction "CLK_11") (pintype "input"))
      (node (ref "DFF4") (pin "3") (pinfunction "CLK_3") (pintype "input"))
      (node (ref "DFF5") (pin "11") (pinfunction "CLK_11") (pintype "input"))
      (node (ref "DFF5") (pin "3") (pinfunction "CLK_3") (pintype "input"))
      (node (ref "DFF6") (pin "11") (pinfunction "CLK_11") (pintype "input"))
      (node (ref "DFF6") (pin "3") (pinfunction "CLK_3") (pintype "input"))
      (node (ref "DFF7") (pin "11") (pinfunction "CLK_11") (pintype "input"))
      (node (ref "DFF7") (pin "3") (pinfunction "CLK_3") (pintype "input"))
      (node (ref "DFF8") (pin "11") (pinfunction "CLK_11") (pintype "input"))
      (node (ref "DFF8") (pin "3") (pinfunction "CLK_3") (pintype "input"))
      (node (ref "PLD1") (pin "1") (pinfunction "I/CLK_1") (pintype "bidirectional"))
      (node (ref "PLD2") (pin "1") (pinfunction "I/CLK_1") (pintype "bidirectional"))
      (node (ref "PLD3") (pin "1") (pinfunction "I/CLK_1") (pintype "bidirectional"))
    )
    (net (code "68") (name "unconnected-(CLK-NC-Pad1)") (class "Default")
      (node (ref "CLK") (pin "1") (pinfunction "NC_1") (pintype "passive"))
    )
    (net (code "69") (name "unconnected-(DFF1A-CLR-Pad1)") (class "Default")
      (node (ref "DFF1") (pin "1") (pinfunction "CLR_1") (pintype "input+no_connect"))
    )
    (net (code "70") (name "unconnected-(DFF1A-PR-Pad4)") (class "Default")
      (node (ref "DFF1") (pin "4") (pinfunction "PR_4") (pintype "input+no_connect"))
    )
    (net (code "71") (name "unconnected-(DFF1A-~{Q}-Pad6)") (class "Default")
      (node (ref "DFF1") (pin "6") (pinfunction "~{Q}_6") (pintype "output+no_connect"))
    )
    (net (code "72") (name "unconnected-(DFF1B-CLR-Pad13)") (class "Default")
      (node (ref "DFF1") (pin "13") (pinfunction "CLR_13") (pintype "input+no_connect"))
    )
    (net (code "73") (name "unconnected-(DFF1B-PR-Pad10)") (class "Default")
      (node (ref "DFF1") (pin "10") (pinfunction "PR_10") (pintype "input+no_connect"))
    )
    (net (code "74") (name "unconnected-(DFF1B-~{Q}-Pad8)") (class "Default")
      (node (ref "DFF1") (pin "8") (pinfunction "~{Q}_8") (pintype "output+no_connect"))
    )
    (net (code "75") (name "unconnected-(DFF2A-CLR-Pad1)") (class "Default")
      (node (ref "DFF2") (pin "1") (pinfunction "CLR_1") (pintype "input+no_connect"))
    )
    (net (code "76") (name "unconnected-(DFF2A-PR-Pad4)") (class "Default")
      (node (ref "DFF2") (pin "4") (pinfunction "PR_4") (pintype "input+no_connect"))
    )
    (net (code "77") (name "unconnected-(DFF2A-~{Q}-Pad6)") (class "Default")
      (node (ref "DFF2") (pin "6") (pinfunction "~{Q}_6") (pintype "output+no_connect"))
    )
    (net (code "78") (name "unconnected-(DFF2B-CLR-Pad13)") (class "Default")
      (node (ref "DFF2") (pin "13") (pinfunction "CLR_13") (pintype "input+no_connect"))
    )
    (net (code "79") (name "unconnected-(DFF2B-PR-Pad10)") (class "Default")
      (node (ref "DFF2") (pin "10") (pinfunction "PR_10") (pintype "input+no_connect"))
    )
    (net (code "80") (name "unconnected-(DFF2B-~{Q}-Pad8)") (class "Default")
      (node (ref "DFF2") (pin "8") (pinfunction "~{Q}_8") (pintype "output+no_connect"))
    )
    (net (code "81") (name "unconnected-(DFF3A-CLR-Pad1)") (class "Default")
      (node (ref "DFF3") (pin "1") (pinfunction "CLR_1") (pintype "input+no_connect"))
    )
    (net (code "82") (name "unconnected-(DFF3A-PR-Pad4)") (class "Default")
      (node (ref "DFF3") (pin "4") (pinfunction "PR_4") (pintype "input+no_connect"))
    )
    (net (code "83") (name "unconnected-(DFF3A-~{Q}-Pad6)") (class "Default")
      (node (ref "DFF3") (pin "6") (pinfunction "~{Q}_6") (pintype "output+no_connect"))
    )
    (net (code "84") (name "unconnected-(DFF3B-CLR-Pad13)") (class "Default")
      (node (ref "DFF3") (pin "13") (pinfunction "CLR_13") (pintype "input+no_connect"))
    )
    (net (code "85") (name "unconnected-(DFF3B-PR-Pad10)") (class "Default")
      (node (ref "DFF3") (pin "10") (pinfunction "PR_10") (pintype "input+no_connect"))
    )
    (net (code "86") (name "unconnected-(DFF3B-~{Q}-Pad8)") (class "Default")
      (node (ref "DFF3") (pin "8") (pinfunction "~{Q}_8") (pintype "output+no_connect"))
    )
    (net (code "87") (name "unconnected-(DFF4A-CLR-Pad1)") (class "Default")
      (node (ref "DFF4") (pin "1") (pinfunction "CLR_1") (pintype "input+no_connect"))
    )
    (net (code "88") (name "unconnected-(DFF4A-PR-Pad4)") (class "Default")
      (node (ref "DFF4") (pin "4") (pinfunction "PR_4") (pintype "input+no_connect"))
    )
    (net (code "89") (name "unconnected-(DFF4A-~{Q}-Pad6)") (class "Default")
      (node (ref "DFF4") (pin "6") (pinfunction "~{Q}_6") (pintype "output+no_connect"))
    )
    (net (code "90") (name "unconnected-(DFF4B-CLR-Pad13)") (class "Default")
      (node (ref "DFF4") (pin "13") (pinfunction "CLR_13") (pintype "input+no_connect"))
    )
    (net (code "91") (name "unconnected-(DFF4B-PR-Pad10)") (class "Default")
      (node (ref "DFF4") (pin "10") (pinfunction "PR_10") (pintype "input+no_connect"))
    )
    (net (code "92") (name "unconnected-(DFF4B-~{Q}-Pad8)") (class "Default")
      (node (ref "DFF4") (pin "8") (pinfunction "~{Q}_8") (pintype "output+no_connect"))
    )
    (net (code "93") (name "unconnected-(DFF5A-CLR-Pad1)") (class "Default")
      (node (ref "DFF5") (pin "1") (pinfunction "CLR_1") (pintype "input+no_connect"))
    )
    (net (code "94") (name "unconnected-(DFF5A-PR-Pad4)") (class "Default")
      (node (ref "DFF5") (pin "4") (pinfunction "PR_4") (pintype "input+no_connect"))
    )
    (net (code "95") (name "unconnected-(DFF5A-~{Q}-Pad6)") (class "Default")
      (node (ref "DFF5") (pin "6") (pinfunction "~{Q}_6") (pintype "output+no_connect"))
    )
    (net (code "96") (name "unconnected-(DFF5B-CLR-Pad13)") (class "Default")
      (node (ref "DFF5") (pin "13") (pinfunction "CLR_13") (pintype "input+no_connect"))
    )
    (net (code "97") (name "unconnected-(DFF5B-PR-Pad10)") (class "Default")
      (node (ref "DFF5") (pin "10") (pinfunction "PR_10") (pintype "input+no_connect"))
    )
    (net (code "98") (name "unconnected-(DFF5B-~{Q}-Pad8)") (class "Default")
      (node (ref "DFF5") (pin "8") (pinfunction "~{Q}_8") (pintype "output+no_connect"))
    )
    (net (code "99") (name "unconnected-(DFF6A-CLR-Pad1)") (class "Default")
      (node (ref "DFF6") (pin "1") (pinfunction "CLR_1") (pintype "input+no_connect"))
    )
    (net (code "100") (name "unconnected-(DFF6A-PR-Pad4)") (class "Default")
      (node (ref "DFF6") (pin "4") (pinfunction "PR_4") (pintype "input+no_connect"))
    )
    (net (code "101") (name "unconnected-(DFF6A-~{Q}-Pad6)") (class "Default")
      (node (ref "DFF6") (pin "6") (pinfunction "~{Q}_6") (pintype "output+no_connect"))
    )
    (net (code "102") (name "unconnected-(DFF6B-CLR-Pad13)") (class "Default")
      (node (ref "DFF6") (pin "13") (pinfunction "CLR_13") (pintype "input+no_connect"))
    )
    (net (code "103") (name "unconnected-(DFF6B-PR-Pad10)") (class "Default")
      (node (ref "DFF6") (pin "10") (pinfunction "PR_10") (pintype "input+no_connect"))
    )
    (net (code "104") (name "unconnected-(DFF6B-~{Q}-Pad8)") (class "Default")
      (node (ref "DFF6") (pin "8") (pinfunction "~{Q}_8") (pintype "output+no_connect"))
    )
    (net (code "105") (name "unconnected-(DFF7A-CLR-Pad1)") (class "Default")
      (node (ref "DFF7") (pin "1") (pinfunction "CLR_1") (pintype "input+no_connect"))
    )
    (net (code "106") (name "unconnected-(DFF7A-PR-Pad4)") (class "Default")
      (node (ref "DFF7") (pin "4") (pinfunction "PR_4") (pintype "input+no_connect"))
    )
    (net (code "107") (name "unconnected-(DFF7A-~{Q}-Pad6)") (class "Default")
      (node (ref "DFF7") (pin "6") (pinfunction "~{Q}_6") (pintype "output+no_connect"))
    )
    (net (code "108") (name "unconnected-(DFF7B-CLR-Pad13)") (class "Default")
      (node (ref "DFF7") (pin "13") (pinfunction "CLR_13") (pintype "input+no_connect"))
    )
    (net (code "109") (name "unconnected-(DFF7B-PR-Pad10)") (class "Default")
      (node (ref "DFF7") (pin "10") (pinfunction "PR_10") (pintype "input+no_connect"))
    )
    (net (code "110") (name "unconnected-(DFF7B-~{Q}-Pad8)") (class "Default")
      (node (ref "DFF7") (pin "8") (pinfunction "~{Q}_8") (pintype "output+no_connect"))
    )
    (net (code "111") (name "unconnected-(DFF8A-CLR-Pad1)") (class "Default")
      (node (ref "DFF8") (pin "1") (pinfunction "CLR_1") (pintype "input+no_connect"))
    )
    (net (code "112") (name "unconnected-(DFF8A-PR-Pad4)") (class "Default")
      (node (ref "DFF8") (pin "4") (pinfunction "PR_4") (pintype "input+no_connect"))
    )
    (net (code "113") (name "unconnected-(DFF8A-~{Q}-Pad6)") (class "Default")
      (node (ref "DFF8") (pin "6") (pinfunction "~{Q}_6") (pintype "output"))
    )
    (net (code "114") (name "unconnected-(DFF8B-CLR-Pad13)") (class "Default")
      (node (ref "DFF8") (pin "13") (pinfunction "CLR_13") (pintype "input+no_connect"))
    )
    (net (code "115") (name "unconnected-(DFF8B-PR-Pad10)") (class "Default")
      (node (ref "DFF8") (pin "10") (pinfunction "PR_10") (pintype "input+no_connect"))
    )
    (net (code "116") (name "unconnected-(DFF8B-~{Q}-Pad8)") (class "Default")
      (node (ref "DFF8") (pin "8") (pinfunction "~{Q}_8") (pintype "output+no_connect"))
    )
    (net (code "117") (name "unconnected-(MCU-3V3-Pad1)") (class "Default")
      (node (ref "MCU") (pin "1") (pinfunction "3V3_1") (pintype "output+no_connect"))
    )
    (net (code "118") (name "unconnected-(MCU-D2-Pad4)") (class "Default")
      (node (ref "MCU") (pin "4") (pinfunction "D2_4") (pintype "bidirectional+no_connect"))
    )
    (net (code "119") (name "unconnected-(MCU-D4-Pad5)") (class "Default")
      (node (ref "MCU") (pin "5") (pinfunction "D4_5") (pintype "bidirectional+no_connect"))
    )
    (net (code "120") (name "unconnected-(MCU-D5-Pad8)") (class "Default")
      (node (ref "MCU") (pin "8") (pinfunction "D5_8") (pintype "bidirectional+no_connect"))
    )
    (net (code "121") (name "unconnected-(MCU-D12-Pad27)") (class "Default")
      (node (ref "MCU") (pin "27") (pinfunction "D12_27") (pintype "bidirectional+no_connect"))
    )
    (net (code "122") (name "unconnected-(MCU-D15-Pad3)") (class "Default")
      (node (ref "MCU") (pin "3") (pinfunction "D15_3") (pintype "bidirectional+no_connect"))
    )
    (net (code "123") (name "unconnected-(MCU-EN-Pad16)") (class "Default")
      (node (ref "MCU") (pin "16") (pinfunction "EN_16") (pintype "input+no_connect"))
    )
    (net (code "124") (name "unconnected-(MCU-RX0-Pad12)") (class "Default")
      (node (ref "MCU") (pin "12") (pinfunction "RX0_12") (pintype "input+no_connect"))
    )
    (net (code "125") (name "unconnected-(MCU-RX2-Pad6)") (class "Default")
      (node (ref "MCU") (pin "6") (pinfunction "RX2_6") (pintype "input+no_connect"))
    )
    (net (code "126") (name "unconnected-(MCU-TX0-Pad13)") (class "Default")
      (node (ref "MCU") (pin "13") (pinfunction "TX0_13") (pintype "output+no_connect"))
    )
    (net (code "127") (name "unconnected-(MCU-TX2-Pad7)") (class "Default")
      (node (ref "MCU") (pin "7") (pinfunction "TX2_7") (pintype "output+no_connect"))
    )
    (net (code "128") (name "unconnected-(PLD1-I5-Pad6)") (class "Default")
      (node (ref "PLD1") (pin "6") (pinfunction "I5_6") (pintype "input+no_connect"))
    )
    (net (code "129") (name "unconnected-(PLD1-I6-Pad7)") (class "Default")
      (node (ref "PLD1") (pin "7") (pinfunction "I6_7") (pintype "input+no_connect"))
    )
    (net (code "130") (name "unconnected-(PLD1-I7-Pad8)") (class "Default")
      (node (ref "PLD1") (pin "8") (pinfunction "I7_8") (pintype "input+no_connect"))
    )
    (net (code "131") (name "unconnected-(PLD1-I8-Pad9)") (class "Default")
      (node (ref "PLD1") (pin "9") (pinfunction "I8_9") (pintype "input+no_connect"))
    )
    (net (code "132") (name "unconnected-(PLD1-I9{slash}OE-Pad11)") (class "Default")
      (node (ref "PLD1") (pin "11") (pinfunction "I9/OE_11") (pintype "bidirectional+no_connect"))
    )
    (net (code "133") (name "unconnected-(PLD2-I9{slash}OE-Pad11)") (class "Default")
      (node (ref "PLD2") (pin "11") (pinfunction "I9/OE_11") (pintype "bidirectional+no_connect"))
    )
    (net (code "134") (name "unconnected-(PLD2-I{slash}O-Pad12)") (class "Default")
      (node (ref "PLD2") (pin "12") (pinfunction "I/O_12") (pintype "bidirectional+no_connect"))
    )
    (net (code "135") (name "unconnected-(PLD2-I{slash}O-Pad13)") (class "Default")
      (node (ref "PLD2") (pin "13") (pinfunction "I/O_13") (pintype "bidirectional+no_connect"))
    )
    (net (code "136") (name "unconnected-(PLD2-I{slash}O-Pad14)") (class "Default")
      (node (ref "PLD2") (pin "14") (pinfunction "I/O_14") (pintype "bidirectional+no_connect"))
    )
    (net (code "137") (name "unconnected-(PLD2-I{slash}O-Pad15)") (class "Default")
      (node (ref "PLD2") (pin "15") (pinfunction "I/O_15") (pintype "bidirectional+no_connect"))
    )
    (net (code "138") (name "unconnected-(PLD2-I{slash}O-Pad16)") (class "Default")
      (node (ref "PLD2") (pin "16") (pinfunction "I/O_16") (pintype "bidirectional+no_connect"))
    )
    (net (code "139") (name "unconnected-(PLD2-I{slash}O-Pad17)") (class "Default")
      (node (ref "PLD2") (pin "17") (pinfunction "I/O_17") (pintype "bidirectional+no_connect"))
    )
    (net (code "140") (name "unconnected-(PLD3-I9{slash}OE-Pad11)") (class "Default")
      (node (ref "PLD3") (pin "11") (pinfunction "I9/OE_11") (pintype "bidirectional+no_connect"))
    )
    (net (code "141") (name "unconnected-(PLD3-I{slash}O-Pad12)") (class "Default")
      (node (ref "PLD3") (pin "12") (pinfunction "I/O_12") (pintype "bidirectional+no_connect"))
    )
    (net (code "142") (name "unconnected-(PLD3-I{slash}O-Pad13)") (class "Default")
      (node (ref "PLD3") (pin "13") (pinfunction "I/O_13") (pintype "bidirectional+no_connect"))
    )
    (net (code "143") (name "unconnected-(PLD3-I{slash}O-Pad14)") (class "Default")
      (node (ref "PLD3") (pin "14") (pinfunction "I/O_14") (pintype "bidirectional+no_connect"))
    )
    (net (code "144") (name "unconnected-(PLD3-I{slash}O-Pad15)") (class "Default")
      (node (ref "PLD3") (pin "15") (pinfunction "I/O_15") (pintype "bidirectional+no_connect"))
    )
    (net (code "145") (name "unconnected-(PLD3-I{slash}O-Pad16)") (class "Default")
      (node (ref "PLD3") (pin "16") (pinfunction "I/O_16") (pintype "bidirectional+no_connect"))
    )
    (net (code "146") (name "unconnected-(PLD3-I{slash}O-Pad17)") (class "Default")
      (node (ref "PLD3") (pin "17") (pinfunction "I/O_17") (pintype "bidirectional+no_connect"))
    )
    (net (code "147") (name "unconnected-(S1-Pad4)") (class "Default")
      (node (ref "S1") (pin "4") (pinfunction "4_4") (pintype "passive+no_connect"))
    )
    (net (code "148") (name "unconnected-(S2-Pad4)") (class "Default")
      (node (ref "S2") (pin "4") (pinfunction "4_4") (pintype "passive+no_connect"))
    )
    (net (code "149") (name "unconnected-(S3-Pad4)") (class "Default")
      (node (ref "S3") (pin "4") (pinfunction "4_4") (pintype "passive+no_connect"))
    )
  )
)
